# BGA_Modules.net
KiCad netlist of a schematic drawn in Altium Designer
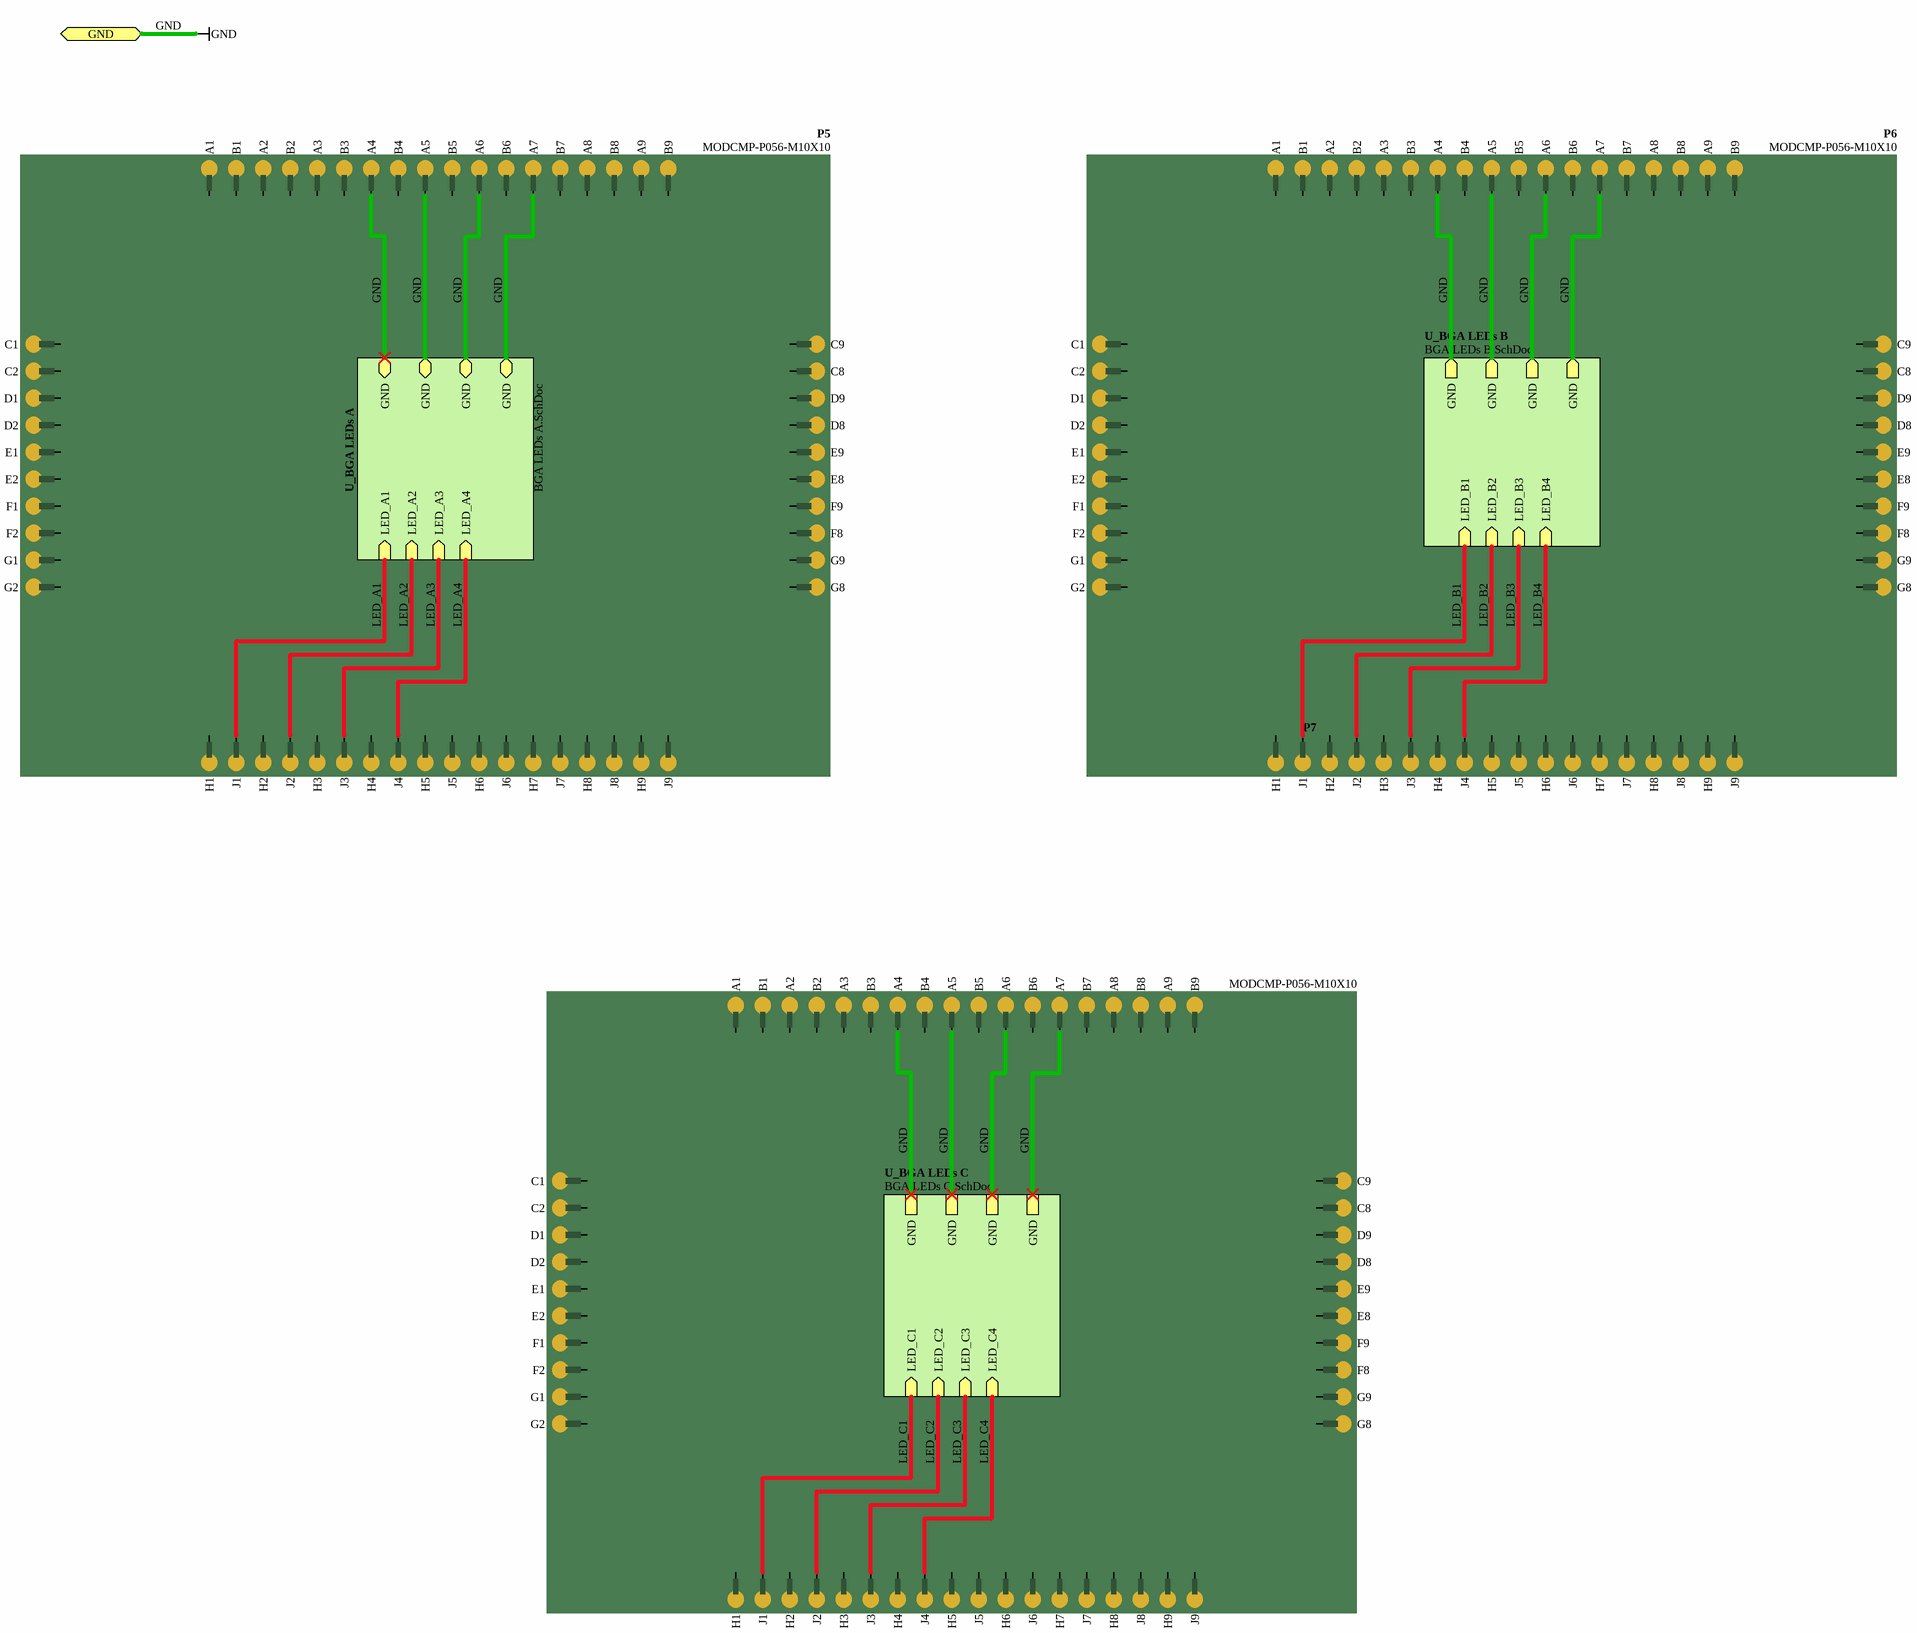
[diagram p0: BGA Modules.SchDoc]

(export (version "E")
  (design (tool "Eeschema 10.0.6"))
  (components
    (comp (ref "P5")
      (value "MODCMP-P056-M10X10")
      (footprint "MODCMP-P056-M10X10")
      (description "Module Component - 1mm Pitch, 56-Pin, 10mmX10mm")
      (libsource (lib "Component_DB") (part "MODCMP-P056-M10X10"))
    )
    (comp (ref "P6")
      (value "MODCMP-P056-M10X10")
      (footprint "MODCMP-P056-M10X10")
      (description "Module Component - 1mm Pitch, 56-Pin, 10mmX10mm")
      (libsource (lib "Component_DB") (part "MODCMP-P056-M10X10"))
    )
    (comp (ref "P7")
      (value "MODCMP-P056-M10X10")
      (footprint "MODCMP-P056-M10X10")
      (description "Module Component - 1mm Pitch, 56-Pin, 10mmX10mm")
      (libsource (lib "Component_DB") (part "MODCMP-P056-M10X10"))
    )
  )
  (nets
    (net (code "1") (name "/LED_A1") (class "Default")
      (node (ref "P5") (pin "J1") (pinfunction "J1_J1") (pintype "passive"))
    )
    (net (code "2") (name "/LED_A2") (class "Default")
      (node (ref "P5") (pin "J2") (pinfunction "J2_J2") (pintype "passive"))
    )
    (net (code "3") (name "/LED_A3") (class "Default")
      (node (ref "P5") (pin "J3") (pinfunction "J3_J3") (pintype "passive"))
    )
    (net (code "4") (name "/LED_A4") (class "Default")
      (node (ref "P5") (pin "J4") (pinfunction "J4_J4") (pintype "passive"))
    )
    (net (code "5") (name "/LED_B1") (class "Default")
      (node (ref "P6") (pin "J1") (pinfunction "J1_J1") (pintype "passive"))
    )
    (net (code "6") (name "/LED_B2") (class "Default")
      (node (ref "P6") (pin "J2") (pinfunction "J2_J2") (pintype "passive"))
    )
    (net (code "7") (name "/LED_B3") (class "Default")
      (node (ref "P6") (pin "J3") (pinfunction "J3_J3") (pintype "passive"))
    )
    (net (code "8") (name "/LED_B4") (class "Default")
      (node (ref "P6") (pin "J4") (pinfunction "J4_J4") (pintype "passive"))
    )
    (net (code "9") (name "/LED_C1") (class "Default")
      (node (ref "P7") (pin "J1") (pinfunction "J1_J1") (pintype "passive"))
    )
    (net (code "10") (name "/LED_C2") (class "Default")
      (node (ref "P7") (pin "J2") (pinfunction "J2_J2") (pintype "passive"))
    )
    (net (code "11") (name "/LED_C3") (class "Default")
      (node (ref "P7") (pin "J3") (pinfunction "J3_J3") (pintype "passive"))
    )
    (net (code "12") (name "/LED_C4") (class "Default")
      (node (ref "P7") (pin "J4") (pinfunction "J4_J4") (pintype "passive"))
    )
    (net (code "13") (name "GND") (class "Default")
      (node (ref "P5") (pin "A4") (pinfunction "A4_A4") (pintype "passive"))
      (node (ref "P5") (pin "A5") (pinfunction "A5_A5") (pintype "passive"))
      (node (ref "P5") (pin "A6") (pinfunction "A6_A6") (pintype "passive"))
      (node (ref "P5") (pin "A7") (pinfunction "A7_A7") (pintype "passive"))
      (node (ref "P6") (pin "A4") (pinfunction "A4_A4") (pintype "passive"))
      (node (ref "P6") (pin "A5") (pinfunction "A5_A5") (pintype "passive"))
      (node (ref "P6") (pin "A6") (pinfunction "A6_A6") (pintype "passive"))
      (node (ref "P6") (pin "A7") (pinfunction "A7_A7") (pintype "passive"))
      (node (ref "P7") (pin "A4") (pinfunction "A4_A4") (pintype "passive"))
      (node (ref "P7") (pin "A5") (pinfunction "A5_A5") (pintype "passive"))
      (node (ref "P7") (pin "A6") (pinfunction "A6_A6") (pintype "passive"))
      (node (ref "P7") (pin "A7") (pinfunction "A7_A7") (pintype "passive"))
    )
    (net (code "14") (name "unconnected-(P5-PadA1)") (class "Default")
      (node (ref "P5") (pin "A1") (pinfunction "A1_A1") (pintype "passive"))
    )
    (net (code "15") (name "unconnected-(P5-PadA2)") (class "Default")
      (node (ref "P5") (pin "A2") (pinfunction "A2_A2") (pintype "passive"))
    )
    (net (code "16") (name "unconnected-(P5-PadA3)") (class "Default")
      (node (ref "P5") (pin "A3") (pinfunction "A3_A3") (pintype "passive"))
    )
    (net (code "17") (name "unconnected-(P5-PadA8)") (class "Default")
      (node (ref "P5") (pin "A8") (pinfunction "A8_A8") (pintype "passive"))
    )
    (net (code "18") (name "unconnected-(P5-PadA9)") (class "Default")
      (node (ref "P5") (pin "A9") (pinfunction "A9_A9") (pintype "passive"))
    )
    (net (code "19") (name "unconnected-(P5-PadB1)") (class "Default")
      (node (ref "P5") (pin "B1") (pinfunction "B1_B1") (pintype "passive"))
    )
    (net (code "20") (name "unconnected-(P5-PadB2)") (class "Default")
      (node (ref "P5") (pin "B2") (pinfunction "B2_B2") (pintype "passive"))
    )
    (net (code "21") (name "unconnected-(P5-PadB3)") (class "Default")
      (node (ref "P5") (pin "B3") (pinfunction "B3_B3") (pintype "passive"))
    )
    (net (code "22") (name "unconnected-(P5-PadB4)") (class "Default")
      (node (ref "P5") (pin "B4") (pinfunction "B4_B4") (pintype "passive"))
    )
    (net (code "23") (name "unconnected-(P5-PadB5)") (class "Default")
      (node (ref "P5") (pin "B5") (pinfunction "B5_B5") (pintype "passive"))
    )
    (net (code "24") (name "unconnected-(P5-PadB6)") (class "Default")
      (node (ref "P5") (pin "B6") (pinfunction "B6_B6") (pintype "passive"))
    )
    (net (code "25") (name "unconnected-(P5-PadB7)") (class "Default")
      (node (ref "P5") (pin "B7") (pinfunction "B7_B7") (pintype "passive"))
    )
    (net (code "26") (name "unconnected-(P5-PadB8)") (class "Default")
      (node (ref "P5") (pin "B8") (pinfunction "B8_B8") (pintype "passive"))
    )
    (net (code "27") (name "unconnected-(P5-PadB9)") (class "Default")
      (node (ref "P5") (pin "B9") (pinfunction "B9_B9") (pintype "passive"))
    )
    (net (code "28") (name "unconnected-(P5-PadC1)") (class "Default")
      (node (ref "P5") (pin "C1") (pinfunction "C1_C1") (pintype "passive"))
    )
    (net (code "29") (name "unconnected-(P5-PadC2)") (class "Default")
      (node (ref "P5") (pin "C2") (pinfunction "C2_C2") (pintype "passive"))
    )
    (net (code "30") (name "unconnected-(P5-PadC8)") (class "Default")
      (node (ref "P5") (pin "C8") (pinfunction "C8_C8") (pintype "passive"))
    )
    (net (code "31") (name "unconnected-(P5-PadC9)") (class "Default")
      (node (ref "P5") (pin "C9") (pinfunction "C9_C9") (pintype "passive"))
    )
    (net (code "32") (name "unconnected-(P5-PadD1)") (class "Default")
      (node (ref "P5") (pin "D1") (pinfunction "D1_D1") (pintype "passive"))
    )
    (net (code "33") (name "unconnected-(P5-PadD2)") (class "Default")
      (node (ref "P5") (pin "D2") (pinfunction "D2_D2") (pintype "passive"))
    )
    (net (code "34") (name "unconnected-(P5-PadD8)") (class "Default")
      (node (ref "P5") (pin "D8") (pinfunction "D8_D8") (pintype "passive"))
    )
    (net (code "35") (name "unconnected-(P5-PadD9)") (class "Default")
      (node (ref "P5") (pin "D9") (pinfunction "D9_D9") (pintype "passive"))
    )
    (net (code "36") (name "unconnected-(P5-PadE1)") (class "Default")
      (node (ref "P5") (pin "E1") (pinfunction "E1_E1") (pintype "passive"))
    )
    (net (code "37") (name "unconnected-(P5-PadE2)") (class "Default")
      (node (ref "P5") (pin "E2") (pinfunction "E2_E2") (pintype "passive"))
    )
    (net (code "38") (name "unconnected-(P5-PadE8)") (class "Default")
      (node (ref "P5") (pin "E8") (pinfunction "E8_E8") (pintype "passive"))
    )
    (net (code "39") (name "unconnected-(P5-PadE9)") (class "Default")
      (node (ref "P5") (pin "E9") (pinfunction "E9_E9") (pintype "passive"))
    )
    (net (code "40") (name "unconnected-(P5-PadF1)") (class "Default")
      (node (ref "P5") (pin "F1") (pinfunction "F1_F1") (pintype "passive"))
    )
    (net (code "41") (name "unconnected-(P5-PadF2)") (class "Default")
      (node (ref "P5") (pin "F2") (pinfunction "F2_F2") (pintype "passive"))
    )
    (net (code "42") (name "unconnected-(P5-PadF8)") (class "Default")
      (node (ref "P5") (pin "F8") (pinfunction "F8_F8") (pintype "passive"))
    )
    (net (code "43") (name "unconnected-(P5-PadF9)") (class "Default")
      (node (ref "P5") (pin "F9") (pinfunction "F9_F9") (pintype "passive"))
    )
    (net (code "44") (name "unconnected-(P5-PadG1)") (class "Default")
      (node (ref "P5") (pin "G1") (pinfunction "G1_G1") (pintype "passive"))
    )
    (net (code "45") (name "unconnected-(P5-PadG2)") (class "Default")
      (node (ref "P5") (pin "G2") (pinfunction "G2_G2") (pintype "passive"))
    )
    (net (code "46") (name "unconnected-(P5-PadG8)") (class "Default")
      (node (ref "P5") (pin "G8") (pinfunction "G8_G8") (pintype "passive"))
    )
    (net (code "47") (name "unconnected-(P5-PadG9)") (class "Default")
      (node (ref "P5") (pin "G9") (pinfunction "G9_G9") (pintype "passive"))
    )
    (net (code "48") (name "unconnected-(P5-PadH1)") (class "Default")
      (node (ref "P5") (pin "H1") (pinfunction "H1_H1") (pintype "passive"))
    )
    (net (code "49") (name "unconnected-(P5-PadH2)") (class "Default")
      (node (ref "P5") (pin "H2") (pinfunction "H2_H2") (pintype "passive"))
    )
    (net (code "50") (name "unconnected-(P5-PadH3)") (class "Default")
      (node (ref "P5") (pin "H3") (pinfunction "H3_H3") (pintype "passive"))
    )
    (net (code "51") (name "unconnected-(P5-PadH4)") (class "Default")
      (node (ref "P5") (pin "H4") (pinfunction "H4_H4") (pintype "passive"))
    )
    (net (code "52") (name "unconnected-(P5-PadH5)") (class "Default")
      (node (ref "P5") (pin "H5") (pinfunction "H5_H5") (pintype "passive"))
    )
    (net (code "53") (name "unconnected-(P5-PadH6)") (class "Default")
      (node (ref "P5") (pin "H6") (pinfunction "H6_H6") (pintype "passive"))
    )
    (net (code "54") (name "unconnected-(P5-PadH7)") (class "Default")
      (node (ref "P5") (pin "H7") (pinfunction "H7_H7") (pintype "passive"))
    )
    (net (code "55") (name "unconnected-(P5-PadH8)") (class "Default")
      (node (ref "P5") (pin "H8") (pinfunction "H8_H8") (pintype "passive"))
    )
    (net (code "56") (name "unconnected-(P5-PadH9)") (class "Default")
      (node (ref "P5") (pin "H9") (pinfunction "H9_H9") (pintype "passive"))
    )
    (net (code "57") (name "unconnected-(P5-PadJ5)") (class "Default")
      (node (ref "P5") (pin "J5") (pinfunction "J5_J5") (pintype "passive"))
    )
    (net (code "58") (name "unconnected-(P5-PadJ6)") (class "Default")
      (node (ref "P5") (pin "J6") (pinfunction "J6_J6") (pintype "passive"))
    )
    (net (code "59") (name "unconnected-(P5-PadJ7)") (class "Default")
      (node (ref "P5") (pin "J7") (pinfunction "J7_J7") (pintype "passive"))
    )
    (net (code "60") (name "unconnected-(P5-PadJ8)") (class "Default")
      (node (ref "P5") (pin "J8") (pinfunction "J8_J8") (pintype "passive"))
    )
    (net (code "61") (name "unconnected-(P5-PadJ9)") (class "Default")
      (node (ref "P5") (pin "J9") (pinfunction "J9_J9") (pintype "passive"))
    )
    (net (code "62") (name "unconnected-(P6-PadA1)") (class "Default")
      (node (ref "P6") (pin "A1") (pinfunction "A1_A1") (pintype "passive"))
    )
    (net (code "63") (name "unconnected-(P6-PadA2)") (class "Default")
      (node (ref "P6") (pin "A2") (pinfunction "A2_A2") (pintype "passive"))
    )
    (net (code "64") (name "unconnected-(P6-PadA3)") (class "Default")
      (node (ref "P6") (pin "A3") (pinfunction "A3_A3") (pintype "passive"))
    )
    (net (code "65") (name "unconnected-(P6-PadA8)") (class "Default")
      (node (ref "P6") (pin "A8") (pinfunction "A8_A8") (pintype "passive"))
    )
    (net (code "66") (name "unconnected-(P6-PadA9)") (class "Default")
      (node (ref "P6") (pin "A9") (pinfunction "A9_A9") (pintype "passive"))
    )
    (net (code "67") (name "unconnected-(P6-PadB1)") (class "Default")
      (node (ref "P6") (pin "B1") (pinfunction "B1_B1") (pintype "passive"))
    )
    (net (code "68") (name "unconnected-(P6-PadB2)") (class "Default")
      (node (ref "P6") (pin "B2") (pinfunction "B2_B2") (pintype "passive"))
    )
    (net (code "69") (name "unconnected-(P6-PadB3)") (class "Default")
      (node (ref "P6") (pin "B3") (pinfunction "B3_B3") (pintype "passive"))
    )
    (net (code "70") (name "unconnected-(P6-PadB4)") (class "Default")
      (node (ref "P6") (pin "B4") (pinfunction "B4_B4") (pintype "passive"))
    )
    (net (code "71") (name "unconnected-(P6-PadB5)") (class "Default")
      (node (ref "P6") (pin "B5") (pinfunction "B5_B5") (pintype "passive"))
    )
    (net (code "72") (name "unconnected-(P6-PadB6)") (class "Default")
      (node (ref "P6") (pin "B6") (pinfunction "B6_B6") (pintype "passive"))
    )
    (net (code "73") (name "unconnected-(P6-PadB7)") (class "Default")
      (node (ref "P6") (pin "B7") (pinfunction "B7_B7") (pintype "passive"))
    )
    (net (code "74") (name "unconnected-(P6-PadB8)") (class "Default")
      (node (ref "P6") (pin "B8") (pinfunction "B8_B8") (pintype "passive"))
    )
    (net (code "75") (name "unconnected-(P6-PadB9)") (class "Default")
      (node (ref "P6") (pin "B9") (pinfunction "B9_B9") (pintype "passive"))
    )
    (net (code "76") (name "unconnected-(P6-PadC1)") (class "Default")
      (node (ref "P6") (pin "C1") (pinfunction "C1_C1") (pintype "passive"))
    )
    (net (code "77") (name "unconnected-(P6-PadC2)") (class "Default")
      (node (ref "P6") (pin "C2") (pinfunction "C2_C2") (pintype "passive"))
    )
    (net (code "78") (name "unconnected-(P6-PadC8)") (class "Default")
      (node (ref "P6") (pin "C8") (pinfunction "C8_C8") (pintype "passive"))
    )
    (net (code "79") (name "unconnected-(P6-PadC9)") (class "Default")
      (node (ref "P6") (pin "C9") (pinfunction "C9_C9") (pintype "passive"))
    )
    (net (code "80") (name "unconnected-(P6-PadD1)") (class "Default")
      (node (ref "P6") (pin "D1") (pinfunction "D1_D1") (pintype "passive"))
    )
    (net (code "81") (name "unconnected-(P6-PadD2)") (class "Default")
      (node (ref "P6") (pin "D2") (pinfunction "D2_D2") (pintype "passive"))
    )
    (net (code "82") (name "unconnected-(P6-PadD8)") (class "Default")
      (node (ref "P6") (pin "D8") (pinfunction "D8_D8") (pintype "passive"))
    )
    (net (code "83") (name "unconnected-(P6-PadD9)") (class "Default")
      (node (ref "P6") (pin "D9") (pinfunction "D9_D9") (pintype "passive"))
    )
    (net (code "84") (name "unconnected-(P6-PadE1)") (class "Default")
      (node (ref "P6") (pin "E1") (pinfunction "E1_E1") (pintype "passive"))
    )
    (net (code "85") (name "unconnected-(P6-PadE2)") (class "Default")
      (node (ref "P6") (pin "E2") (pinfunction "E2_E2") (pintype "passive"))
    )
    (net (code "86") (name "unconnected-(P6-PadE8)") (class "Default")
      (node (ref "P6") (pin "E8") (pinfunction "E8_E8") (pintype "passive"))
    )
    (net (code "87") (name "unconnected-(P6-PadE9)") (class "Default")
      (node (ref "P6") (pin "E9") (pinfunction "E9_E9") (pintype "passive"))
    )
    (net (code "88") (name "unconnected-(P6-PadF1)") (class "Default")
      (node (ref "P6") (pin "F1") (pinfunction "F1_F1") (pintype "passive"))
    )
    (net (code "89") (name "unconnected-(P6-PadF2)") (class "Default")
      (node (ref "P6") (pin "F2") (pinfunction "F2_F2") (pintype "passive"))
    )
    (net (code "90") (name "unconnected-(P6-PadF8)") (class "Default")
      (node (ref "P6") (pin "F8") (pinfunction "F8_F8") (pintype "passive"))
    )
    (net (code "91") (name "unconnected-(P6-PadF9)") (class "Default")
      (node (ref "P6") (pin "F9") (pinfunction "F9_F9") (pintype "passive"))
    )
    (net (code "92") (name "unconnected-(P6-PadG1)") (class "Default")
      (node (ref "P6") (pin "G1") (pinfunction "G1_G1") (pintype "passive"))
    )
    (net (code "93") (name "unconnected-(P6-PadG2)") (class "Default")
      (node (ref "P6") (pin "G2") (pinfunction "G2_G2") (pintype "passive"))
    )
    (net (code "94") (name "unconnected-(P6-PadG8)") (class "Default")
      (node (ref "P6") (pin "G8") (pinfunction "G8_G8") (pintype "passive"))
    )
    (net (code "95") (name "unconnected-(P6-PadG9)") (class "Default")
      (node (ref "P6") (pin "G9") (pinfunction "G9_G9") (pintype "passive"))
    )
    (net (code "96") (name "unconnected-(P6-PadH1)") (class "Default")
      (node (ref "P6") (pin "H1") (pinfunction "H1_H1") (pintype "passive"))
    )
    (net (code "97") (name "unconnected-(P6-PadH2)") (class "Default")
      (node (ref "P6") (pin "H2") (pinfunction "H2_H2") (pintype "passive"))
    )
    (net (code "98") (name "unconnected-(P6-PadH3)") (class "Default")
      (node (ref "P6") (pin "H3") (pinfunction "H3_H3") (pintype "passive"))
    )
    (net (code "99") (name "unconnected-(P6-PadH4)") (class "Default")
      (node (ref "P6") (pin "H4") (pinfunction "H4_H4") (pintype "passive"))
    )
    (net (code "100") (name "unconnected-(P6-PadH5)") (class "Default")
      (node (ref "P6") (pin "H5") (pinfunction "H5_H5") (pintype "passive"))
    )
    (net (code "101") (name "unconnected-(P6-PadH6)") (class "Default")
      (node (ref "P6") (pin "H6") (pinfunction "H6_H6") (pintype "passive"))
    )
    (net (code "102") (name "unconnected-(P6-PadH7)") (class "Default")
      (node (ref "P6") (pin "H7") (pinfunction "H7_H7") (pintype "passive"))
    )
    (net (code "103") (name "unconnected-(P6-PadH8)") (class "Default")
      (node (ref "P6") (pin "H8") (pinfunction "H8_H8") (pintype "passive"))
    )
    (net (code "104") (name "unconnected-(P6-PadH9)") (class "Default")
      (node (ref "P6") (pin "H9") (pinfunction "H9_H9") (pintype "passive"))
    )
    (net (code "105") (name "unconnected-(P6-PadJ5)") (class "Default")
      (node (ref "P6") (pin "J5") (pinfunction "J5_J5") (pintype "passive"))
    )
    (net (code "106") (name "unconnected-(P6-PadJ6)") (class "Default")
      (node (ref "P6") (pin "J6") (pinfunction "J6_J6") (pintype "passive"))
    )
    (net (code "107") (name "unconnected-(P6-PadJ7)") (class "Default")
      (node (ref "P6") (pin "J7") (pinfunction "J7_J7") (pintype "passive"))
    )
    (net (code "108") (name "unconnected-(P6-PadJ8)") (class "Default")
      (node (ref "P6") (pin "J8") (pinfunction "J8_J8") (pintype "passive"))
    )
    (net (code "109") (name "unconnected-(P6-PadJ9)") (class "Default")
      (node (ref "P6") (pin "J9") (pinfunction "J9_J9") (pintype "passive"))
    )
    (net (code "110") (name "unconnected-(P7-PadA1)") (class "Default")
      (node (ref "P7") (pin "A1") (pinfunction "A1_A1") (pintype "passive"))
    )
    (net (code "111") (name "unconnected-(P7-PadA2)") (class "Default")
      (node (ref "P7") (pin "A2") (pinfunction "A2_A2") (pintype "passive"))
    )
    (net (code "112") (name "unconnected-(P7-PadA3)") (class "Default")
      (node (ref "P7") (pin "A3") (pinfunction "A3_A3") (pintype "passive"))
    )
    (net (code "113") (name "unconnected-(P7-PadA8)") (class "Default")
      (node (ref "P7") (pin "A8") (pinfunction "A8_A8") (pintype "passive"))
    )
    (net (code "114") (name "unconnected-(P7-PadA9)") (class "Default")
      (node (ref "P7") (pin "A9") (pinfunction "A9_A9") (pintype "passive"))
    )
    (net (code "115") (name "unconnected-(P7-PadB1)") (class "Default")
      (node (ref "P7") (pin "B1") (pinfunction "B1_B1") (pintype "passive"))
    )
    (net (code "116") (name "unconnected-(P7-PadB2)") (class "Default")
      (node (ref "P7") (pin "B2") (pinfunction "B2_B2") (pintype "passive"))
    )
    (net (code "117") (name "unconnected-(P7-PadB3)") (class "Default")
      (node (ref "P7") (pin "B3") (pinfunction "B3_B3") (pintype "passive"))
    )
    (net (code "118") (name "unconnected-(P7-PadB4)") (class "Default")
      (node (ref "P7") (pin "B4") (pinfunction "B4_B4") (pintype "passive"))
    )
    (net (code "119") (name "unconnected-(P7-PadB5)") (class "Default")
      (node (ref "P7") (pin "B5") (pinfunction "B5_B5") (pintype "passive"))
    )
    (net (code "120") (name "unconnected-(P7-PadB6)") (class "Default")
      (node (ref "P7") (pin "B6") (pinfunction "B6_B6") (pintype "passive"))
    )
    (net (code "121") (name "unconnected-(P7-PadB7)") (class "Default")
      (node (ref "P7") (pin "B7") (pinfunction "B7_B7") (pintype "passive"))
    )
    (net (code "122") (name "unconnected-(P7-PadB8)") (class "Default")
      (node (ref "P7") (pin "B8") (pinfunction "B8_B8") (pintype "passive"))
    )
    (net (code "123") (name "unconnected-(P7-PadB9)") (class "Default")
      (node (ref "P7") (pin "B9") (pinfunction "B9_B9") (pintype "passive"))
    )
    (net (code "124") (name "unconnected-(P7-PadC1)") (class "Default")
      (node (ref "P7") (pin "C1") (pinfunction "C1_C1") (pintype "passive"))
    )
    (net (code "125") (name "unconnected-(P7-PadC2)") (class "Default")
      (node (ref "P7") (pin "C2") (pinfunction "C2_C2") (pintype "passive"))
    )
    (net (code "126") (name "unconnected-(P7-PadC8)") (class "Default")
      (node (ref "P7") (pin "C8") (pinfunction "C8_C8") (pintype "passive"))
    )
    (net (code "127") (name "unconnected-(P7-PadC9)") (class "Default")
      (node (ref "P7") (pin "C9") (pinfunction "C9_C9") (pintype "passive"))
    )
    (net (code "128") (name "unconnected-(P7-PadD1)") (class "Default")
      (node (ref "P7") (pin "D1") (pinfunction "D1_D1") (pintype "passive"))
    )
    (net (code "129") (name "unconnected-(P7-PadD2)") (class "Default")
      (node (ref "P7") (pin "D2") (pinfunction "D2_D2") (pintype "passive"))
    )
    (net (code "130") (name "unconnected-(P7-PadD8)") (class "Default")
      (node (ref "P7") (pin "D8") (pinfunction "D8_D8") (pintype "passive"))
    )
    (net (code "131") (name "unconnected-(P7-PadD9)") (class "Default")
      (node (ref "P7") (pin "D9") (pinfunction "D9_D9") (pintype "passive"))
    )
    (net (code "132") (name "unconnected-(P7-PadE1)") (class "Default")
      (node (ref "P7") (pin "E1") (pinfunction "E1_E1") (pintype "passive"))
    )
    (net (code "133") (name "unconnected-(P7-PadE2)") (class "Default")
      (node (ref "P7") (pin "E2") (pinfunction "E2_E2") (pintype "passive"))
    )
    (net (code "134") (name "unconnected-(P7-PadE8)") (class "Default")
      (node (ref "P7") (pin "E8") (pinfunction "E8_E8") (pintype "passive"))
    )
    (net (code "135") (name "unconnected-(P7-PadE9)") (class "Default")
      (node (ref "P7") (pin "E9") (pinfunction "E9_E9") (pintype "passive"))
    )
    (net (code "136") (name "unconnected-(P7-PadF1)") (class "Default")
      (node (ref "P7") (pin "F1") (pinfunction "F1_F1") (pintype "passive"))
    )
    (net (code "137") (name "unconnected-(P7-PadF2)") (class "Default")
      (node (ref "P7") (pin "F2") (pinfunction "F2_F2") (pintype "passive"))
    )
    (net (code "138") (name "unconnected-(P7-PadF8)") (class "Default")
      (node (ref "P7") (pin "F8") (pinfunction "F8_F8") (pintype "passive"))
    )
    (net (code "139") (name "unconnected-(P7-PadF9)") (class "Default")
      (node (ref "P7") (pin "F9") (pinfunction "F9_F9") (pintype "passive"))
    )
    (net (code "140") (name "unconnected-(P7-PadG1)") (class "Default")
      (node (ref "P7") (pin "G1") (pinfunction "G1_G1") (pintype "passive"))
    )
    (net (code "141") (name "unconnected-(P7-PadG2)") (class "Default")
      (node (ref "P7") (pin "G2") (pinfunction "G2_G2") (pintype "passive"))
    )
    (net (code "142") (name "unconnected-(P7-PadG8)") (class "Default")
      (node (ref "P7") (pin "G8") (pinfunction "G8_G8") (pintype "passive"))
    )
    (net (code "143") (name "unconnected-(P7-PadG9)") (class "Default")
      (node (ref "P7") (pin "G9") (pinfunction "G9_G9") (pintype "passive"))
    )
    (net (code "144") (name "unconnected-(P7-PadH1)") (class "Default")
      (node (ref "P7") (pin "H1") (pinfunction "H1_H1") (pintype "passive"))
    )
    (net (code "145") (name "unconnected-(P7-PadH2)") (class "Default")
      (node (ref "P7") (pin "H2") (pinfunction "H2_H2") (pintype "passive"))
    )
    (net (code "146") (name "unconnected-(P7-PadH3)") (class "Default")
      (node (ref "P7") (pin "H3") (pinfunction "H3_H3") (pintype "passive"))
    )
    (net (code "147") (name "unconnected-(P7-PadH4)") (class "Default")
      (node (ref "P7") (pin "H4") (pinfunction "H4_H4") (pintype "passive"))
    )
    (net (code "148") (name "unconnected-(P7-PadH5)") (class "Default")
      (node (ref "P7") (pin "H5") (pinfunction "H5_H5") (pintype "passive"))
    )
    (net (code "149") (name "unconnected-(P7-PadH6)") (class "Default")
      (node (ref "P7") (pin "H6") (pinfunction "H6_H6") (pintype "passive"))
    )
    (net (code "150") (name "unconnected-(P7-PadH7)") (class "Default")
      (node (ref "P7") (pin "H7") (pinfunction "H7_H7") (pintype "passive"))
    )
    (net (code "151") (name "unconnected-(P7-PadH8)") (class "Default")
      (node (ref "P7") (pin "H8") (pinfunction "H8_H8") (pintype "passive"))
    )
    (net (code "152") (name "unconnected-(P7-PadH9)") (class "Default")
      (node (ref "P7") (pin "H9") (pinfunction "H9_H9") (pintype "passive"))
    )
    (net (code "153") (name "unconnected-(P7-PadJ5)") (class "Default")
      (node (ref "P7") (pin "J5") (pinfunction "J5_J5") (pintype "passive"))
    )
    (net (code "154") (name "unconnected-(P7-PadJ6)") (class "Default")
      (node (ref "P7") (pin "J6") (pinfunction "J6_J6") (pintype "passive"))
    )
    (net (code "155") (name "unconnected-(P7-PadJ7)") (class "Default")
      (node (ref "P7") (pin "J7") (pinfunction "J7_J7") (pintype "passive"))
    )
    (net (code "156") (name "unconnected-(P7-PadJ8)") (class "Default")
      (node (ref "P7") (pin "J8") (pinfunction "J8_J8") (pintype "passive"))
    )
    (net (code "157") (name "unconnected-(P7-PadJ9)") (class "Default")
      (node (ref "P7") (pin "J9") (pinfunction "J9_J9") (pintype "passive"))
    )
  )
)
